# Sheet1.net
KiCad netlist of a schematic drawn in Altium Designer
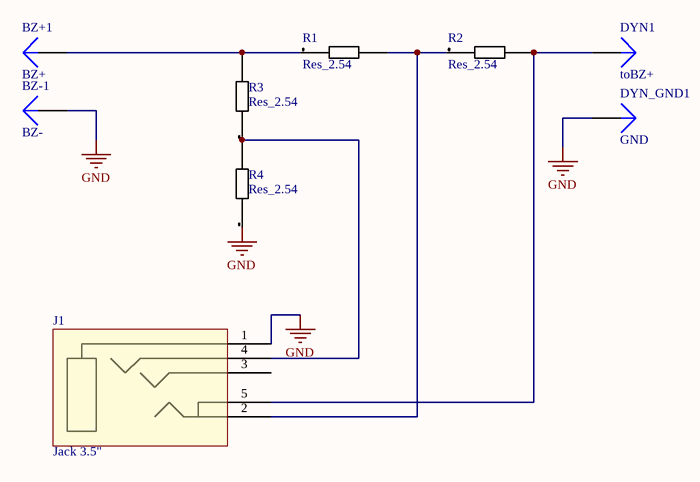
[diagram p0: Sheet1.SchDoc]

(export (version "E")
  (design (tool "Eeschema 10.0.6"))
  (components
    (comp (ref "BZ+1")
      (value "BZ+")
      (footprint "Solder PAD 4*4")
      (description "Plug")
      (fields (field (name "PUBLISHER") "Altium Limited"))
      (libsource (lib "Miscellaneous Connectors") (part "Plug"))
    )
    (comp (ref "BZ-1")
      (value "BZ-")
      (footprint "Solder PAD 4*4")
      (description "Plug")
      (fields (field (name "PUBLISHER") "Altium Limited"))
      (libsource (lib "Miscellaneous Connectors") (part "Plug"))
    )
    (comp (ref "DYN1")
      (value "toBZ+")
      (footprint "Solder PAD 4*4")
      (description "Plug")
      (fields (field (name "PUBLISHER") "Altium Limited"))
      (libsource (lib "Miscellaneous Connectors") (part "Plug"))
    )
    (comp (ref "DYN_GND1")
      (value "GND")
      (footprint "Solder PAD 4*4")
      (description "Plug")
      (fields (field (name "PUBLISHER") "Altium Limited"))
      (libsource (lib "Miscellaneous Connectors") (part "Plug"))
    )
    (comp (ref "J1")
      (value "Jack 3.5\"")
      (footprint "micro SJ-43515TS-SMT - duplicate - duplicate")
      (description "miniJack 4 contact")
      (libsource (lib "TiLib") (part "PhoneJack 4contact"))
    )
    (comp (ref "R1")
      (value "Res_2.54")
      (footprint "1608[0603]-Xs1.0Ys1.1A0.76RR_RES")
      (description "Resistor")
      (libsource (lib "") (part "Res_2.54_1"))
    )
    (comp (ref "R2")
      (value "Res_2.54")
      (footprint "1608[0603]-Xs1.0Ys1.1A0.76RR_RES")
      (description "Resistor")
      (libsource (lib "") (part "Res_2.54_1"))
    )
    (comp (ref "R3")
      (value "Res_2.54")
      (footprint "1608[0603]-Xs1.0Ys1.1A0.76RR_RES")
      (description "Resistor")
      (libsource (lib "SLib") (part "Res_2.54"))
    )
    (comp (ref "R4")
      (value "Res_2.54")
      (footprint "1608[0603]-Xs1.0Ys1.1A0.76RR_RES")
      (description "Resistor")
      (libsource (lib "SLib") (part "Res_2.54"))
    )
  )
  (nets
    (net (code "1") (name "GND") (class "Default")
      (node (ref "BZ-1") (pin "1") (pinfunction "1_1") (pintype "passive"))
      (node (ref "DYN_GND1") (pin "1") (pinfunction "1_1") (pintype "passive"))
      (node (ref "J1") (pin "1") (pinfunction "1_1") (pintype "passive"))
      (node (ref "R4") (pin "1") (pinfunction "1_1") (pintype "passive"))
    )
    (net (code "2") (name "Net-(BZ+1-Pad1)") (class "Default")
      (node (ref "BZ+1") (pin "1") (pinfunction "1_1") (pintype "passive"))
      (node (ref "R1") (pin "1") (pinfunction "1_1") (pintype "passive"))
      (node (ref "R3") (pin "2") (pinfunction "2_2") (pintype "passive"))
    )
    (net (code "3") (name "Net-(DYN1-Pad1)") (class "Default")
      (node (ref "DYN1") (pin "1") (pinfunction "1_1") (pintype "passive"))
      (node (ref "J1") (pin "5") (pinfunction "5_5") (pintype "passive"))
      (node (ref "R2") (pin "2") (pinfunction "2_2") (pintype "passive"))
    )
    (net (code "4") (name "Net-(J1-Pad2)") (class "Default")
      (node (ref "J1") (pin "2") (pinfunction "2_2") (pintype "passive"))
      (node (ref "R1") (pin "2") (pinfunction "2_2") (pintype "passive"))
      (node (ref "R2") (pin "1") (pinfunction "1_1") (pintype "passive"))
    )
    (net (code "5") (name "Net-(J1-Pad4)") (class "Default")
      (node (ref "J1") (pin "4") (pinfunction "4_4") (pintype "passive"))
      (node (ref "R3") (pin "1") (pinfunction "1_1") (pintype "passive"))
      (node (ref "R4") (pin "2") (pinfunction "2_2") (pintype "passive"))
    )
    (net (code "6") (name "unconnected-(J1-Pad3)") (class "Default")
      (node (ref "J1") (pin "3") (pinfunction "3_3") (pintype "passive"))
    )
  )
)
